# MicroSDCard.net
KiCad netlist of a schematic drawn in Altium Designer
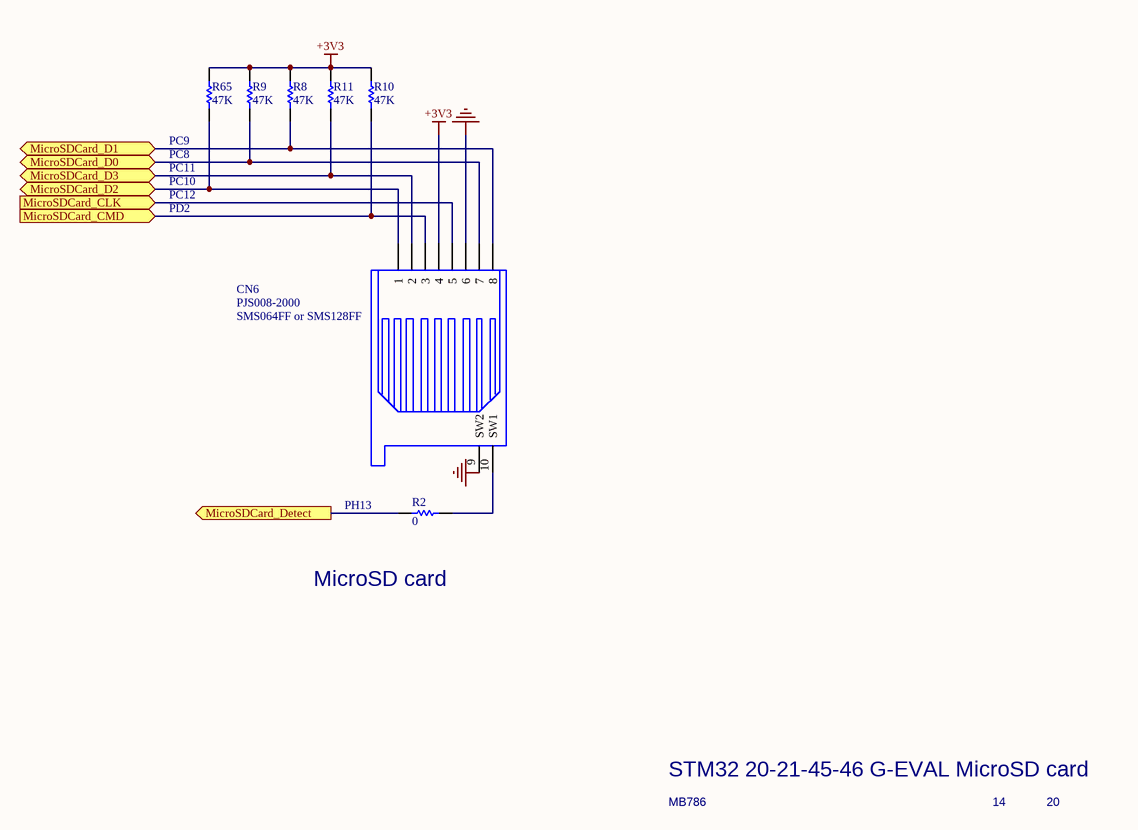
[diagram p0: MicroSDCard.SchDoc]

(export (version "E")
  (design (tool "Eeschema 10.0.6"))
  (components
    (comp (ref "CN6")
      (value "PJS008-2000")
      (footprint "MSD(PJS008)")
      (libsource (lib "MB525") (part "SMS016AFA5E"))
    )
    (comp (ref "R2")
      (value "0")
      (footprint "0603R")
      (description "Resistor")
      (fields (field (name "PUBLISHER") "Altium Limited"))
      (libsource (lib "Miscellaneous Devices") (part "Res1"))
    )
    (comp (ref "R8")
      (value "47K")
      (footprint "0402R")
      (description "Resistor")
      (fields (field (name "PUBLISHER") "Altium Limited"))
      (libsource (lib "Miscellaneous Devices") (part "Res1"))
    )
    (comp (ref "R9")
      (value "47K")
      (footprint "0402R")
      (description "Resistor")
      (fields (field (name "PUBLISHER") "Altium Limited"))
      (libsource (lib "Miscellaneous Devices") (part "Res1"))
    )
    (comp (ref "R10")
      (value "47K")
      (footprint "0402R")
      (description "Resistor")
      (fields (field (name "PUBLISHER") "Altium Limited"))
      (libsource (lib "Miscellaneous Devices") (part "Res1"))
    )
    (comp (ref "R11")
      (value "47K")
      (footprint "0402R")
      (description "Resistor")
      (fields (field (name "PUBLISHER") "Altium Limited"))
      (libsource (lib "Miscellaneous Devices") (part "Res1"))
    )
    (comp (ref "R65")
      (value "47K")
      (footprint "0402R")
      (description "Resistor")
      (fields (field (name "PUBLISHER") "Altium Limited"))
      (libsource (lib "Miscellaneous Devices") (part "Res1"))
    )
  )
  (nets
    (net (code "1") (name "+3V3") (class "Default")
      (node (ref "CN6") (pin "4") (pinfunction "4_4") (pintype "passive"))
      (node (ref "R10") (pin "1") (pinfunction "1_1") (pintype "passive"))
      (node (ref "R11") (pin "1") (pinfunction "1_1") (pintype "passive"))
      (node (ref "R65") (pin "1") (pinfunction "1_1") (pintype "passive"))
      (node (ref "R8") (pin "1") (pinfunction "1_1") (pintype "passive"))
      (node (ref "R9") (pin "1") (pinfunction "1_1") (pintype "passive"))
    )
    (net (code "2") (name "/MicroSDCard_CLK") (class "Default")
      (node (ref "CN6") (pin "5") (pinfunction "5_5") (pintype "passive"))
    )
    (net (code "3") (name "/MicroSDCard_CMD") (class "Default")
      (node (ref "CN6") (pin "3") (pinfunction "3_3") (pintype "passive"))
      (node (ref "R10") (pin "2") (pinfunction "2_2") (pintype "passive"))
    )
    (net (code "4") (name "/MicroSDCard_D0") (class "Default")
      (node (ref "CN6") (pin "7") (pinfunction "7_7") (pintype "passive"))
      (node (ref "R9") (pin "2") (pinfunction "2_2") (pintype "passive"))
    )
    (net (code "5") (name "/MicroSDCard_D1") (class "Default")
      (node (ref "CN6") (pin "8") (pinfunction "8_8") (pintype "passive"))
      (node (ref "R8") (pin "2") (pinfunction "2_2") (pintype "passive"))
    )
    (net (code "6") (name "/MicroSDCard_D2") (class "Default")
      (node (ref "CN6") (pin "1") (pinfunction "1_1") (pintype "passive"))
      (node (ref "R65") (pin "2") (pinfunction "2_2") (pintype "passive"))
    )
    (net (code "7") (name "/MicroSDCard_D3") (class "Default")
      (node (ref "CN6") (pin "2") (pinfunction "2_2") (pintype "passive"))
      (node (ref "R11") (pin "2") (pinfunction "2_2") (pintype "passive"))
    )
    (net (code "8") (name "/MicroSDCard_Detect") (class "Default")
      (node (ref "R2") (pin "1") (pinfunction "1_1") (pintype "passive"))
    )
    (net (code "9") (name "GND") (class "Default")
      (node (ref "CN6") (pin "6") (pinfunction "6_6") (pintype "passive"))
      (node (ref "CN6") (pin "9") (pinfunction "SW2_9") (pintype "passive"))
    )
    (net (code "10") (name "Net-(CN6-SW1)") (class "Default")
      (node (ref "CN6") (pin "10") (pinfunction "SW1_10") (pintype "passive"))
      (node (ref "R2") (pin "2") (pinfunction "2_2") (pintype "passive"))
    )
  )
)
